# LedChannel.net
KiCad netlist of a schematic drawn in Altium Designer
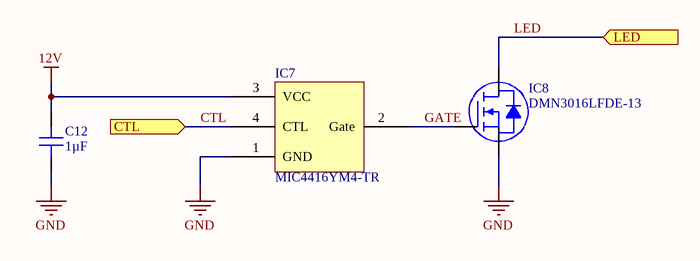
[diagram p0: LedChannel.SchDoc]

(export (version "E")
  (design (tool "Eeschema 10.0.6"))
  (components
    (comp (ref "C12")
      (value "1µF")
      (footprint "CAP 0603_1608")
      (description "CAP CER 1UF 25V X5R 0603")
      (fields
        (field (name "PART NUMBER") "CL10A105KA8NFNC")
        (field (name "MANUFACTURER") "Samsung Electro-Mechanics")
      )
      (libsource (lib "Celestial Altium Library - altium_library") (part "Capacitor"))
    )
    (comp (ref "IC7")
      (value "MIC4416YM4-TR")
      (footprint "MICROCHIP SOT-143-4")
      (description "IC GATE DRVR LOW-SIDE SOT143")
      (fields (field (name "MANUFACTURER") "Microchip Technology"))
      (libsource (lib "Celestial Altium Library - altium_library") (part "MICROCHIP MIC4416"))
    )
    (comp (ref "IC8")
      (value "DMN3016LFDE-13")
      (footprint "DIODES U-DFN2020-6E")
      (description "MOSFET N-CH 30V U-DFN2020-6")
      (fields (field (name "MANUFACTURER") "Diodes Incorporated"))
      (libsource (lib "Celestial Altium Library - altium_library") (part "DIODES INC MOSFET U-DFN2020-6 TYPE E"))
    )
  )
  (nets
    (net (code "1") (name "/CTL") (class "Default")
      (node (ref "IC7") (pin "4") (pinfunction "CTL_4") (pintype "passive"))
    )
    (net (code "2") (name "/GATE") (class "Default")
      (node (ref "IC7") (pin "2") (pinfunction "Gate_2") (pintype "passive"))
      (node (ref "IC8") (pin "G") (pinfunction "G_G") (pintype "passive"))
    )
    (net (code "3") (name "/LED") (class "Default")
      (node (ref "IC8") (pin "D") (pinfunction "Drain_D") (pintype "passive"))
    )
    (net (code "4") (name "12V") (class "Default")
      (node (ref "C12") (pin "2") (pinfunction "2_2") (pintype "passive"))
      (node (ref "IC7") (pin "3") (pinfunction "VCC_3") (pintype "passive"))
    )
    (net (code "5") (name "GND") (class "Default")
      (node (ref "C12") (pin "1") (pinfunction "1_1") (pintype "passive"))
      (node (ref "IC7") (pin "1") (pinfunction "GND_1") (pintype "passive"))
      (node (ref "IC8") (pin "S") (pinfunction "S_S") (pintype "passive"))
    )
  )
)
